# AC-DC_SUPPLY.net
KiCad netlist of a schematic drawn in Altium Designer
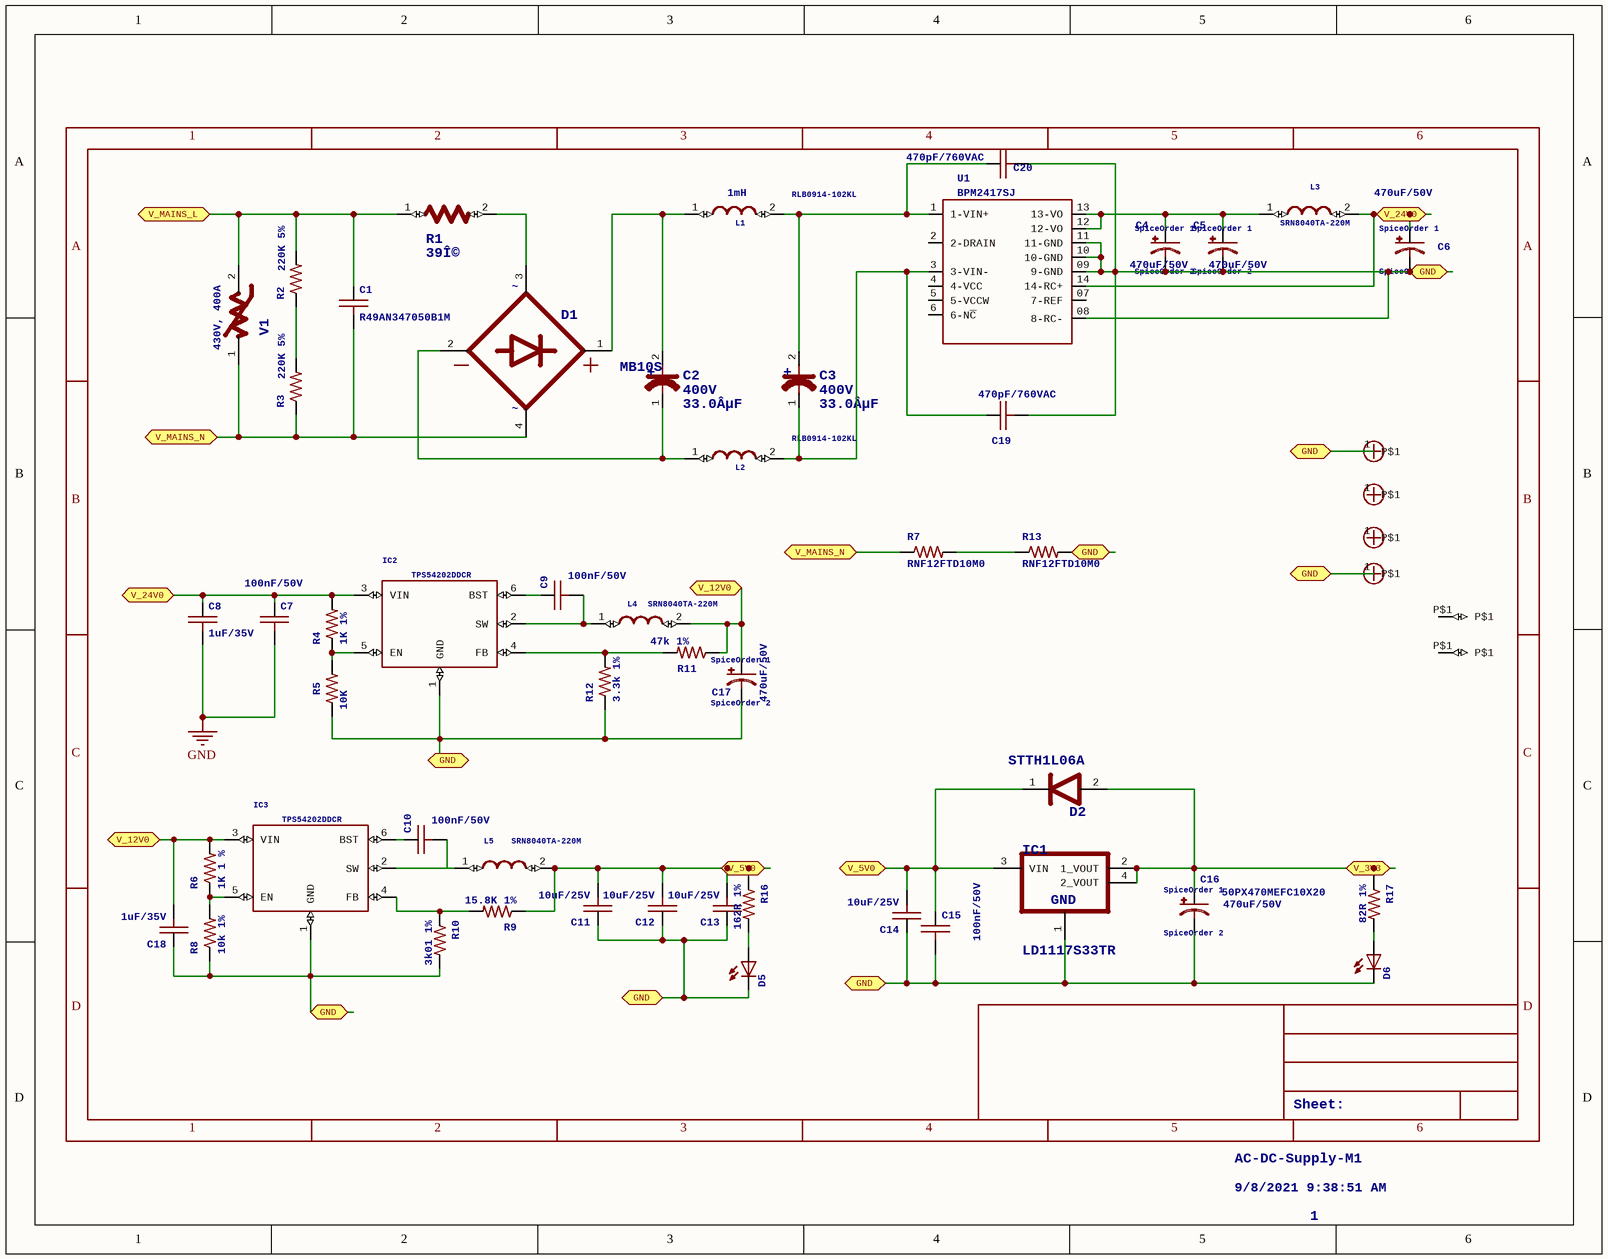
[diagram p0: AC-DC_SUPPLY.SchDoc]

(export (version "E")
  (design (tool "Eeschema 10.0.6"))
  (components
    (comp (ref "C1")
      (value "R49AN347050B1M")
      (footprint "R49AN347050B1M")
      (description "Film,X1,470nF/330Vac,THT")
      (fields (field (name "MFR") "Kemet") (field (name "LIBRARYNAME") "Labops_Lib_AH"))
      (libsource (lib "Labops_Lib_AH") (part "R49AN347050B1M"))
    )
    (comp (ref "C2")
      (value "860011378008")
      (footprint "RADIAL_D13.0P5.0H25.0")
      (description "Electrolytic Cap 33µF 400V 13mm Radial WCAP-ATG8; Lifetime 2000h +85°C")
      (fields
        (field (name "33.0ÂΜF") "33.0碌F")
        (field (name "+") "+")
        (field (name "400V") "400V")
        (field (name "MFR") "Wurth Elektronik")
        (field (name "LIBRARYNAME") "Labops_Lib_AH")
      )
      (libsource (lib "Labops_Lib_AH") (part "860011378008"))
    )
    (comp (ref "C3")
      (value "860011378008")
      (footprint "RADIAL_D13.0P5.0H25.0")
      (description "Electrolytic Cap 33µF 400V 13mm Radial WCAP-ATG8; Lifetime 2000h +85°C")
      (fields
        (field (name "33.0ÂΜF") "33.0碌F")
        (field (name "+") "+")
        (field (name "400V") "400V")
        (field (name "MFR") "Wurth Elektronik")
        (field (name "LIBRARYNAME") "Labops_Lib_AH")
      )
      (libsource (lib "Labops_Lib_AH") (part "860011378008"))
    )
    (comp (ref "C4")
      (value "50PX470MEFC10X20")
      (footprint "CAPACITOR-ELKO-RM5-10X16")
      (description "470uF ±20% 50V 10mm 20mm 5mm 2000Hrs")
      (fields
        (field (name "SPICEORDER1") "SpiceOrder 1")
        (field (name "SPICEORDER2") "SpiceOrder 2")
        (field (name "MFR") "Rubicon")
        (field (name "PART_VALUE") "470uF/50V")
        (field (name "LIBRARYNAME") "Labops_Lib_AH")
      )
      (libsource (lib "Labops_Lib_AH") (part "50PX470MEFC10X20"))
    )
    (comp (ref "C5")
      (value "50PX470MEFC10X20")
      (footprint "CAPACITOR-ELKO-RM5-10X16")
      (description "470uF ±20% 50V 10mm 20mm 5mm 2000Hrs")
      (fields
        (field (name "SPICEORDER1") "SpiceOrder 1")
        (field (name "SPICEORDER2") "SpiceOrder 2")
        (field (name "MFR") "Rubicon")
        (field (name "PART_VALUE") "470uF/50V")
        (field (name "LIBRARYNAME") "Labops_Lib_AH")
      )
      (libsource (lib "Labops_Lib_AH") (part "50PX470MEFC10X20"))
    )
    (comp (ref "C6")
      (value "50PX470MEFC10X20")
      (footprint "CAPACITOR-ELKO-RM5-10X16")
      (description "470uF ±20% 50V 10mm 20mm 5mm 2000Hrs")
      (fields
        (field (name "SPICEORDER1") "SpiceOrder 1")
        (field (name "SPICEORDER2") "SpiceOrder 2")
        (field (name "MFR") "Rubicon")
        (field (name "PART_VALUE") "470uF/50V")
        (field (name "LIBRARYNAME") "Labops_Lib_AH")
      )
      (libsource (lib "Labops_Lib_AH") (part "50PX470MEFC10X20"))
    )
    (comp (ref "C7")
      (value "100nF/50V")
      (footprint "0603")
      (fields (field (name "LIBRARYNAME") "Labops_Lib_AH"))
      (libsource (lib "Labops_Lib_AH") (part "C_0603"))
    )
    (comp (ref "C8")
      (value "1uF/35V")
      (footprint "0603")
      (fields (field (name "LIBRARYNAME") "Labops_Lib_AH"))
      (libsource (lib "Labops_Lib_AH") (part "C_0603"))
    )
    (comp (ref "C9")
      (value "100nF/50V")
      (footprint "0603")
      (fields (field (name "LIBRARYNAME") "Labops_Lib_AH"))
      (libsource (lib "Labops_Lib_AH") (part "C_0603"))
    )
    (comp (ref "C10")
      (value "100nF/50V")
      (footprint "0603")
      (fields (field (name "LIBRARYNAME") "Labops_Lib_AH"))
      (libsource (lib "Labops_Lib_AH") (part "C_0603"))
    )
    (comp (ref "C11")
      (value "10uF/25V")
      (footprint "0603")
      (fields (field (name "LIBRARYNAME") "Labops_Lib_AH"))
      (libsource (lib "Labops_Lib_AH") (part "C_0603"))
    )
    (comp (ref "C12")
      (value "10uF/25V")
      (footprint "0603")
      (fields (field (name "LIBRARYNAME") "Labops_Lib_AH"))
      (libsource (lib "Labops_Lib_AH") (part "C_0603"))
    )
    (comp (ref "C13")
      (value "10uF/25V")
      (footprint "0603")
      (fields (field (name "LIBRARYNAME") "Labops_Lib_AH"))
      (libsource (lib "Labops_Lib_AH") (part "C_0603"))
    )
    (comp (ref "C14")
      (value "10uF/25V")
      (footprint "0603")
      (fields (field (name "LIBRARYNAME") "Labops_Lib_AH"))
      (libsource (lib "Labops_Lib_AH") (part "C_0603"))
    )
    (comp (ref "C15")
      (value "100nF/50V")
      (footprint "0603")
      (fields (field (name "LIBRARYNAME") "Labops_Lib_AH"))
      (libsource (lib "Labops_Lib_AH") (part "C_0603"))
    )
    (comp (ref "C16")
      (value "50PX470MEFC10X20")
      (footprint "CAPACITOR-ELKO-RM5-10X16")
      (description "470uF ±20% 50V 10mm 20mm 5mm 2000Hrs")
      (fields
        (field (name "SPICEORDER1") "SpiceOrder 1")
        (field (name "SPICEORDER2") "SpiceOrder 2")
        (field (name "MFR") "Rubicon")
        (field (name "PART_VALUE") "470uF/50V")
        (field (name "LIBRARYNAME") "Labops_Lib_AH")
      )
      (libsource (lib "Labops_Lib_AH") (part "50PX470MEFC10X20"))
    )
    (comp (ref "C17")
      (value "50PX470MEFC10X20")
      (footprint "CAPACITOR-ELKO-RM5-10X16")
      (description "470uF ±20% 50V 10mm 20mm 5mm 2000Hrs")
      (fields
        (field (name "SPICEORDER1") "SpiceOrder 1")
        (field (name "SPICEORDER2") "SpiceOrder 2")
        (field (name "MFR") "Rubicon")
        (field (name "PART_VALUE") "470uF/50V")
        (field (name "LIBRARYNAME") "Labops_Lib_AH")
      )
      (libsource (lib "Labops_Lib_AH") (part "50PX470MEFC10X20"))
    )
    (comp (ref "C18")
      (value "1uF/35V")
      (footprint "0603")
      (fields (field (name "LIBRARYNAME") "Labops_Lib_AH"))
      (libsource (lib "Labops_Lib_AH") (part "C_0603"))
    )
    (comp (ref "C19")
      (value "ERP610W471MEF0")
      (footprint "CAP-P12.5-H15-W4-D1")
      (description "470 pF ±20% 760VAC Ceramic Capacitor Y5U (E) Radial X1,Y1")
      (fields
        (field (name "MFR") "Kemet")
        (field (name "PART_VALUE") "470pF/760VAC")
        (field (name "LIBRARYNAME") "Labops_Lib_AH")
      )
      (libsource (lib "Labops_Lib_AH") (part "ERP610W471MEF0"))
    )
    (comp (ref "C20")
      (value "ERP610W471MEF0")
      (footprint "CAP-P12.5-H15-W4-D1")
      (description "470 pF ±20% 760VAC Ceramic Capacitor Y5U (E) Radial X1,Y1")
      (fields
        (field (name "MFR") "Kemet")
        (field (name "PART_VALUE") "470pF/760VAC")
        (field (name "LIBRARYNAME") "Labops_Lib_AH")
      )
      (libsource (lib "Labops_Lib_AH") (part "ERP610W471MEF0"))
    )
    (comp (ref "D1")
      (value "MB10S")
      (footprint "SOIC4W")
      (description "0.5 A 1000 V Low Leakage SMT Bridge Rectifier - SOIC-4")
      (fields
        (field (name "MB10S") "MB10S")
        (field (name "MFR") "On Semi, Diodes,MDD")
        (field (name "LIBRARYNAME") "Labops_Lib_AH")
      )
      (libsource (lib "Labops_Lib_AH") (part "MB10S"))
    )
    (comp (ref "D2")
      (value "STTH1L06ASTMICROELECTRONICS_STTH1L06A_0_0")
      (footprint "SMA_STTH1L06A")
      (description "Diode Standard 600V 1A Surface Mount SMA")
      (fields
        (field (name "STTH1L06A") "STTH1L06A")
        (field (name "DIGIKEY_PART_NUMBER") "497-3241-2-ND")
        (field (name "MF") "STMicroelectronics")
        (field (name "LIBRARYNAME") "Labops_Lib_AH")
      )
      (libsource (lib "Labops_Lib_AH") (part "STTH1L06ASTMICROELECTRONICS_STTH1L06A_0_0"))
    )
    (comp (ref "D5")
      (value "26-21/GPC-F3138B/CA")
      (footprint "SMD1206-LED")
      (description "Green SMD LED 1206, 160mcd")
      (fields (field (name "MFR") "Everlight") (field (name "LIBRARYNAME") "Labops_Lib_AH"))
      (libsource (lib "Labops_Lib_AH") (part "26-21/GPC-F3138B/CA"))
    )
    (comp (ref "D6")
      (value "26-21/GPC-F3138B/CA")
      (footprint "SMD1206-LED")
      (description "Green SMD LED 1206, 160mcd")
      (fields (field (name "MFR") "Everlight") (field (name "LIBRARYNAME") "Labops_Lib_AH"))
      (libsource (lib "Labops_Lib_AH") (part "26-21/GPC-F3138B/CA"))
    )
    (comp (ref "FID1")
      (value "FIDUCIAL")
      (footprint "FIDUCIAL")
      (fields (field (name "LIBRARYNAME") "Labops_Lib_AH"))
      (libsource (lib "Labops_Lib_AH") (part "FIDUCIAL"))
    )
    (comp (ref "FID2")
      (value "FIDUCIAL")
      (footprint "FIDUCIAL")
      (fields (field (name "LIBRARYNAME") "Labops_Lib_AH"))
      (libsource (lib "Labops_Lib_AH") (part "FIDUCIAL"))
    )
    (comp (ref "IC1")
      (value "LD1117S33TR")
      (footprint "SOT223_LD1117S33TR")
      (description "LDO,Fixed 15V 3.3V 1.3V")
      (fields
        (field (name "GND") "GND")
        (field (name "LD1117S33TR") "LD1117S33TR")
        (field (name "MFR") "STmicro, Diodes, TI,")
        (field (name "LIBRARYNAME") "Labops_Lib_AH")
      )
      (libsource (lib "Labops_Lib_AH") (part "LD1117S33TR"))
    )
    (comp (ref "IC2")
      (value "TPS54202DDCR")
      (footprint "SOT23-6")
      (description "2A 28V SOT-23-6 Sync Buck")
      (fields (field (name "MFR") "Texas Instruments") (field (name "LIBRARYNAME") "Labops_Lib_AH"))
      (libsource (lib "Labops_Lib_AH") (part "TPS54202DDCR"))
    )
    (comp (ref "IC3")
      (value "TPS54202DDCR")
      (footprint "SOT23-6")
      (description "2A 28V SOT-23-6 Sync Buck")
      (fields (field (name "MFR") "Texas Instruments") (field (name "LIBRARYNAME") "Labops_Lib_AH"))
      (libsource (lib "Labops_Lib_AH") (part "TPS54202DDCR"))
    )
    (comp (ref "L1")
      (value "RLB0914-102KL")
      (footprint "THTINDUCTOR8MM7")
      (description "Inductor Power Wirewound 1mH 10% 252KHz 40Q-Factor Ferrite 300mA 2.1Ohm")
      (fields
        (field (name "MFR") "Bourns")
        (field (name "PART_VALUE") "1mH")
        (field (name "LIBRARYNAME") "Labops_Lib_AH")
      )
      (libsource (lib "Labops_Lib_AH") (part "RLB0914-102KL"))
    )
    (comp (ref "L2")
      (value "RLB0914-102KL")
      (footprint "THTINDUCTOR8MM7")
      (description "Inductor Power Wirewound 1mH 10% 252KHz 40Q-Factor Ferrite 300mA 2.1Ohm")
      (fields (field (name "MFR") "Bourns") (field (name "LIBRARYNAME") "Labops_Lib_AH"))
      (libsource (lib "Labops_Lib_AH") (part "RLB0914-102KL"))
    )
    (comp (ref "L3")
      (value "SRN8040TA-220M")
      (footprint "SRN8040TA-220M")
      (description "FIXED IND 22UH 2.9A SMD, 73m-Ohm, Bourns")
      (fields (field (name "MFR") "Bourns") (field (name "LIBRARYNAME") "Labops_Lib_AH"))
      (libsource (lib "Labops_Lib_AH") (part "SRN8040TA-220M"))
    )
    (comp (ref "L4")
      (value "SRN8040TA-220M")
      (footprint "SRN8040TA-220M")
      (description "FIXED IND 22UH 2.9A SMD, 73m-Ohm, Bourns")
      (fields (field (name "MFR") "Bourns") (field (name "LIBRARYNAME") "Labops_Lib_AH"))
      (libsource (lib "Labops_Lib_AH") (part "SRN8040TA-220M"))
    )
    (comp (ref "L5")
      (value "SRN8040TA-220M")
      (footprint "SRN8040TA-220M")
      (description "FIXED IND 22UH 2.9A SMD, 73m-Ohm, Bourns")
      (fields (field (name "MFR") "Bourns") (field (name "LIBRARYNAME") "Labops_Lib_AH"))
      (libsource (lib "Labops_Lib_AH") (part "SRN8040TA-220M"))
    )
    (comp (ref "M1")
      (value "M_HOLE_3M")
      (footprint "PCB_SCREW_M3_POWER")
      (fields (field (name "LIBRARYNAME") "Labops_Lib_AH"))
      (libsource (lib "Labops_Lib_AH") (part "M_HOLE_3M"))
    )
    (comp (ref "M2")
      (value "M_HOLE_3M")
      (footprint "PCB_SCREW_M3_POWER")
      (fields (field (name "LIBRARYNAME") "Labops_Lib_AH"))
      (libsource (lib "Labops_Lib_AH") (part "M_HOLE_3M"))
    )
    (comp (ref "M3")
      (value "M_HOLE_3M")
      (footprint "PCB_SCREW_M3_POWER")
      (fields (field (name "LIBRARYNAME") "Labops_Lib_AH"))
      (libsource (lib "Labops_Lib_AH") (part "M_HOLE_3M"))
    )
    (comp (ref "M4")
      (value "M_HOLE_3M")
      (footprint "PCB_SCREW_M3_POWER")
      (fields (field (name "LIBRARYNAME") "Labops_Lib_AH"))
      (libsource (lib "Labops_Lib_AH") (part "M_HOLE_3M"))
    )
    (comp (ref "R1")
      (value "ERG-2SJ390V")
      (footprint "ERG-2SJ390V_0")
      (description "RES 39 OHM 2W 5% AXIAL, Metal Oxide, Panasonic")
      (fields (field (name "39惟") "39惟") (field (name "LIBRARYNAME") "Labops_Lib_AH"))
      (libsource (lib "Labops_Lib_AH") (part "ERG-2SJ390V"))
    )
    (comp (ref "R2")
      (value "R_1206")
      (footprint "R1206")
      (fields
        (field (name "MFR") "Vishay")
        (field (name "PART_VALUE") "220K 5%")
        (field (name "LIBRARYNAME") "Labops_Lib_AH")
      )
      (libsource (lib "Labops_Lib_AH") (part "R_1206"))
    )
    (comp (ref "R3")
      (value "R_1206")
      (footprint "R1206")
      (fields
        (field (name "MFR") "Vishay")
        (field (name "PART_VALUE") "220K 5%")
        (field (name "LIBRARYNAME") "Labops_Lib_AH")
      )
      (libsource (lib "Labops_Lib_AH") (part "R_1206"))
    )
    (comp (ref "R4")
      (value "1K 1%")
      (footprint "R0603")
      (fields (field (name "LIBRARYNAME") "Labops_Lib_AH"))
      (libsource (lib "Labops_Lib_AH") (part "R_0603"))
    )
    (comp (ref "R5")
      (value "10K")
      (footprint "R0603")
      (fields (field (name "LIBRARYNAME") "Labops_Lib_AH"))
      (libsource (lib "Labops_Lib_AH") (part "R_0603"))
    )
    (comp (ref "R6")
      (value "1K 1 %")
      (footprint "R0603")
      (fields (field (name "LIBRARYNAME") "Labops_Lib_AH"))
      (libsource (lib "Labops_Lib_AH") (part "R_0603"))
    )
    (comp (ref "R7")
      (value "RNF12FTD10M0")
      (footprint "RES-RM12.5-VR37")
      (description "10 MOhms ±1% 0.5W, 1/2W Through Hole Resistor Axial Flame Retardant Coating, Safety Metal Film")
      (fields (field (name "MFR") "Stackpole Electronics Inc") (field (name "LIBRARYNAME") "Labops_Lib_AH"))
      (libsource (lib "Labops_Lib_AH") (part "RNF12FTD10M0"))
    )
    (comp (ref "R8")
      (value "10k 1%")
      (footprint "R0603")
      (fields (field (name "LIBRARYNAME") "Labops_Lib_AH"))
      (libsource (lib "Labops_Lib_AH") (part "R_0603"))
    )
    (comp (ref "R9")
      (value "15.8K 1%")
      (footprint "R0603")
      (fields (field (name "LIBRARYNAME") "Labops_Lib_AH"))
      (libsource (lib "Labops_Lib_AH") (part "R_0603"))
    )
    (comp (ref "R10")
      (value "3k01 1%")
      (footprint "R0603")
      (fields (field (name "LIBRARYNAME") "Labops_Lib_AH"))
      (libsource (lib "Labops_Lib_AH") (part "R_0603"))
    )
    (comp (ref "R11")
      (value "47k 1%")
      (footprint "R0603")
      (fields (field (name "LIBRARYNAME") "Labops_Lib_AH"))
      (libsource (lib "Labops_Lib_AH") (part "R_0603"))
    )
    (comp (ref "R12")
      (value "3.3k 1%")
      (footprint "R0603")
      (fields (field (name "LIBRARYNAME") "Labops_Lib_AH"))
      (libsource (lib "Labops_Lib_AH") (part "R_0603"))
    )
    (comp (ref "R13")
      (value "RNF12FTD10M0")
      (footprint "RES-RM12.5-VR37")
      (description "10 MOhms ±1% 0.5W, 1/2W Through Hole Resistor Axial Flame Retardant Coating, Safety Metal Film")
      (fields (field (name "MFR") "Stackpole Electronics Inc") (field (name "LIBRARYNAME") "Labops_Lib_AH"))
      (libsource (lib "Labops_Lib_AH") (part "RNF12FTD10M0"))
    )
    (comp (ref "R16")
      (value "162R 1%")
      (footprint "R0603")
      (fields (field (name "LIBRARYNAME") "Labops_Lib_AH"))
      (libsource (lib "Labops_Lib_AH") (part "R_0603"))
    )
    (comp (ref "R17")
      (value "82R 1%")
      (footprint "R0603")
      (fields (field (name "LIBRARYNAME") "Labops_Lib_AH"))
      (libsource (lib "Labops_Lib_AH") (part "R_0603"))
    )
    (comp (ref "U1")
      (value "BPM2417SJ")
      (footprint "BPM2417SJ")
      (description "Ac/Dc Power Supply Module")
      (fields (field (name "MFR") "Tamura") (field (name "LIBRARYNAME") "Labops_Lib_AH"))
      (libsource (lib "Labops_Lib_AH") (part "BPM2417SJ"))
    )
    (comp (ref "V1")
      (value "B72205S0271K101")
      (footprint "EPCOS_B72205S0271K101_0")
      (description "VARISTOR 205V 800A DISC 5MM")
      (fields
        (field (name "MFR") "EPCOS")
        (field (name "PART_VALUE") "430V, 400A")
        (field (name "LIBRARYNAME") "Labops_Lib_AH")
      )
      (libsource (lib "Labops_Lib_AH") (part "B72205S0271K101"))
    )
  )
  (nets
    (net (code "1") (name "/V_3V3") (class "Default")
      (node (ref "C16") (pin "1") (pinfunction "+_1") (pintype "passive"))
      (node (ref "D2") (pin "2") (pinfunction "ANODE_2") (pintype "passive"))
      (node (ref "IC1") (pin "2") (pinfunction "1_VOUT_2") (pintype "power_in"))
      (node (ref "IC1") (pin "4") (pinfunction "2_VOUT_4") (pintype "power_in"))
      (node (ref "R17") (pin "1") (pinfunction "1_1") (pintype "passive"))
    )
    (net (code "2") (name "/V_5V0") (class "Default")
      (node (ref "C11") (pin "2") (pinfunction "2_2") (pintype "passive"))
      (node (ref "C12") (pin "2") (pinfunction "2_2") (pintype "passive"))
      (node (ref "C13") (pin "2") (pinfunction "2_2") (pintype "passive"))
      (node (ref "C14") (pin "2") (pinfunction "2_2") (pintype "passive"))
      (node (ref "C15") (pin "1") (pinfunction "1_1") (pintype "passive"))
      (node (ref "D2") (pin "1") (pinfunction "CATHODE_1") (pintype "passive"))
      (node (ref "IC1") (pin "3") (pinfunction "VIN_3") (pintype "power_in"))
      (node (ref "L5") (pin "2") (pinfunction "P$2_2") (pintype "bidirectional"))
      (node (ref "R16") (pin "1") (pinfunction "1_1") (pintype "passive"))
      (node (ref "R9") (pin "1") (pinfunction "1_1") (pintype "passive"))
    )
    (net (code "3") (name "/V_12V0") (class "Default")
      (node (ref "C17") (pin "1") (pinfunction "+_1") (pintype "passive"))
      (node (ref "C18") (pin "2") (pinfunction "2_2") (pintype "passive"))
      (node (ref "IC3") (pin "3") (pinfunction "VIN_3") (pintype "bidirectional"))
      (node (ref "L4") (pin "2") (pinfunction "P$2_2") (pintype "bidirectional"))
      (node (ref "R11") (pin "1") (pinfunction "1_1") (pintype "passive"))
      (node (ref "R6") (pin "2") (pinfunction "2_2") (pintype "passive"))
    )
    (net (code "4") (name "/V_24V0") (class "Default")
      (node (ref "C6") (pin "1") (pinfunction "+_1") (pintype "passive"))
      (node (ref "C7") (pin "1") (pinfunction "1_1") (pintype "passive"))
      (node (ref "C8") (pin "1") (pinfunction "1_1") (pintype "passive"))
      (node (ref "IC2") (pin "3") (pinfunction "VIN_3") (pintype "bidirectional"))
      (node (ref "L3") (pin "2") (pinfunction "P$2_2") (pintype "bidirectional"))
      (node (ref "R4") (pin "2") (pinfunction "2_2") (pintype "passive"))
      (node (ref "U1") (pin "14") (pinfunction "14-RC+_14") (pintype "bidirectional"))
    )
    (net (code "5") (name "/V_MAINS_L") (class "Default")
      (node (ref "C1") (pin "1") (pinfunction "1_1") (pintype "passive"))
      (node (ref "R1") (pin "1") (pinfunction "1_1") (pintype "bidirectional"))
      (node (ref "R2") (pin "2") (pinfunction "2_2") (pintype "passive"))
      (node (ref "V1") (pin "2") (pinfunction "2_2") (pintype "passive"))
    )
    (net (code "6") (name "/V_MAINS_N") (class "Default")
      (node (ref "C1") (pin "2") (pinfunction "2_2") (pintype "passive"))
      (node (ref "D1") (pin "4") (pinfunction "2_~_4") (pintype "passive"))
      (node (ref "R3") (pin "1") (pinfunction "1_1") (pintype "passive"))
      (node (ref "R7") (pin "1") (pinfunction "1_1") (pintype "passive"))
      (node (ref "V1") (pin "1") (pinfunction "1_1") (pintype "passive"))
    )
    (net (code "7") (name "GND") (class "Default")
      (node (ref "C11") (pin "1") (pinfunction "1_1") (pintype "passive"))
      (node (ref "C12") (pin "1") (pinfunction "1_1") (pintype "passive"))
      (node (ref "C13") (pin "1") (pinfunction "1_1") (pintype "passive"))
      (node (ref "C14") (pin "1") (pinfunction "1_1") (pintype "passive"))
      (node (ref "C15") (pin "2") (pinfunction "2_2") (pintype "passive"))
      (node (ref "C16") (pin "2") (pinfunction "-_2") (pintype "passive"))
      (node (ref "C17") (pin "2") (pinfunction "-_2") (pintype "passive"))
      (node (ref "C18") (pin "1") (pinfunction "1_1") (pintype "passive"))
      (node (ref "C19") (pin "P$2") (pinfunction "2_P$2") (pintype "passive"))
      (node (ref "C20") (pin "P$2") (pinfunction "2_P$2") (pintype "passive"))
      (node (ref "C4") (pin "2") (pinfunction "-_2") (pintype "passive"))
      (node (ref "C5") (pin "2") (pinfunction "-_2") (pintype "passive"))
      (node (ref "C6") (pin "2") (pinfunction "-_2") (pintype "passive"))
      (node (ref "C7") (pin "2") (pinfunction "2_2") (pintype "passive"))
      (node (ref "C8") (pin "2") (pinfunction "2_2") (pintype "passive"))
      (node (ref "D5") (pin "2") (pinfunction "C_2") (pintype "passive"))
      (node (ref "D6") (pin "2") (pinfunction "C_2") (pintype "passive"))
      (node (ref "IC1") (pin "1") (pinfunction "GND_1") (pintype "power_in"))
      (node (ref "IC2") (pin "1") (pinfunction "GND_1") (pintype "bidirectional"))
      (node (ref "IC3") (pin "1") (pinfunction "GND_1") (pintype "bidirectional"))
      (node (ref "M1") (pin "1") (pinfunction "P$1_1") (pintype "bidirectional"))
      (node (ref "M4") (pin "1") (pinfunction "P$1_1") (pintype "bidirectional"))
      (node (ref "R10") (pin "2") (pinfunction "2_2") (pintype "passive"))
      (node (ref "R12") (pin "1") (pinfunction "1_1") (pintype "passive"))
      (node (ref "R13") (pin "2") (pinfunction "2_2") (pintype "passive"))
      (node (ref "R5") (pin "1") (pinfunction "1_1") (pintype "passive"))
      (node (ref "R8") (pin "1") (pinfunction "1_1") (pintype "passive"))
      (node (ref "U1") (pin "08") (pinfunction "8-RC-_08") (pintype "bidirectional"))
      (node (ref "U1") (pin "09") (pinfunction "9-GND_09") (pintype "bidirectional"))
      (node (ref "U1") (pin "10") (pinfunction "10-GND_10") (pintype "bidirectional"))
      (node (ref "U1") (pin "11") (pinfunction "11-GND_11") (pintype "bidirectional"))
    )
    (net (code "8") (name "Net-(C2-ANODE)") (class "Default")
      (node (ref "C2") (pin "2") (pinfunction "ANODE_2") (pintype "passive"))
      (node (ref "D1") (pin "1") (pinfunction "+_1") (pintype "passive"))
      (node (ref "L1") (pin "1") (pinfunction "P$1_1") (pintype "bidirectional"))
    )
    (net (code "9") (name "Net-(C2-CATHODE)") (class "Default")
      (node (ref "C2") (pin "1") (pinfunction "CATHODE_1") (pintype "passive"))
      (node (ref "D1") (pin "2") (pinfunction "-_2") (pintype "passive"))
      (node (ref "L2") (pin "1") (pinfunction "P$1_1") (pintype "bidirectional"))
    )
    (net (code "10") (name "Net-(C4-+)") (class "Default")
      (node (ref "C4") (pin "1") (pinfunction "+_1") (pintype "passive"))
      (node (ref "C5") (pin "1") (pinfunction "+_1") (pintype "passive"))
      (node (ref "L3") (pin "1") (pinfunction "P$1_1") (pintype "bidirectional"))
      (node (ref "U1") (pin "12") (pinfunction "12-VO_12") (pintype "bidirectional"))
      (node (ref "U1") (pin "13") (pinfunction "13-VO_13") (pintype "bidirectional"))
    )
    (net (code "11") (name "Net-(C19-1)") (class "Default")
      (node (ref "C19") (pin "P$1") (pinfunction "1_P$1") (pintype "passive"))
      (node (ref "C3") (pin "1") (pinfunction "CATHODE_1") (pintype "passive"))
      (node (ref "L2") (pin "2") (pinfunction "P$2_2") (pintype "bidirectional"))
      (node (ref "U1") (pin "3") (pinfunction "3-VIN-_3") (pintype "bidirectional"))
    )
    (net (code "12") (name "Net-(C20-1)") (class "Default")
      (node (ref "C20") (pin "P$1") (pinfunction "1_P$1") (pintype "passive"))
      (node (ref "C3") (pin "2") (pinfunction "ANODE_2") (pintype "passive"))
      (node (ref "L1") (pin "2") (pinfunction "P$2_2") (pintype "bidirectional"))
      (node (ref "U1") (pin "1") (pinfunction "1-VIN+_1") (pintype "bidirectional"))
    )
    (net (code "13") (name "Net-(D1-1_~)") (class "Default")
      (node (ref "D1") (pin "3") (pinfunction "1_~_3") (pintype "passive"))
      (node (ref "R1") (pin "2") (pinfunction "2_2") (pintype "bidirectional"))
    )
    (net (code "14") (name "Net-(D5-A)") (class "Default")
      (node (ref "D5") (pin "1") (pinfunction "A_1") (pintype "passive"))
      (node (ref "R16") (pin "2") (pinfunction "2_2") (pintype "passive"))
    )
    (net (code "15") (name "Net-(D6-A)") (class "Default")
      (node (ref "D6") (pin "1") (pinfunction "A_1") (pintype "passive"))
      (node (ref "R17") (pin "2") (pinfunction "2_2") (pintype "passive"))
    )
    (net (code "16") (name "Net-(IC2-BST)") (class "Default")
      (node (ref "C9") (pin "1") (pinfunction "1_1") (pintype "passive"))
      (node (ref "IC2") (pin "6") (pinfunction "BST_6") (pintype "bidirectional"))
    )
    (net (code "17") (name "Net-(IC2-EN)") (class "Default")
      (node (ref "IC2") (pin "5") (pinfunction "EN_5") (pintype "bidirectional"))
      (node (ref "R4") (pin "1") (pinfunction "1_1") (pintype "passive"))
      (node (ref "R5") (pin "2") (pinfunction "2_2") (pintype "passive"))
    )
    (net (code "18") (name "Net-(IC2-FB)") (class "Default")
      (node (ref "IC2") (pin "4") (pinfunction "FB_4") (pintype "bidirectional"))
      (node (ref "R11") (pin "2") (pinfunction "2_2") (pintype "passive"))
      (node (ref "R12") (pin "2") (pinfunction "2_2") (pintype "passive"))
    )
    (net (code "19") (name "Net-(IC2-SW)") (class "Default")
      (node (ref "C9") (pin "2") (pinfunction "2_2") (pintype "passive"))
      (node (ref "IC2") (pin "2") (pinfunction "SW_2") (pintype "bidirectional"))
      (node (ref "L4") (pin "1") (pinfunction "P$1_1") (pintype "bidirectional"))
    )
    (net (code "20") (name "Net-(IC3-BST)") (class "Default")
      (node (ref "C10") (pin "1") (pinfunction "1_1") (pintype "passive"))
      (node (ref "IC3") (pin "6") (pinfunction "BST_6") (pintype "bidirectional"))
    )
    (net (code "21") (name "Net-(IC3-EN)") (class "Default")
      (node (ref "IC3") (pin "5") (pinfunction "EN_5") (pintype "bidirectional"))
      (node (ref "R6") (pin "1") (pinfunction "1_1") (pintype "passive"))
      (node (ref "R8") (pin "2") (pinfunction "2_2") (pintype "passive"))
    )
    (net (code "22") (name "Net-(IC3-FB)") (class "Default")
      (node (ref "IC3") (pin "4") (pinfunction "FB_4") (pintype "bidirectional"))
      (node (ref "R10") (pin "1") (pinfunction "1_1") (pintype "passive"))
      (node (ref "R9") (pin "2") (pinfunction "2_2") (pintype "passive"))
    )
    (net (code "23") (name "Net-(IC3-SW)") (class "Default")
      (node (ref "C10") (pin "2") (pinfunction "2_2") (pintype "passive"))
      (node (ref "IC3") (pin "2") (pinfunction "SW_2") (pintype "bidirectional"))
      (node (ref "L5") (pin "1") (pinfunction "P$1_1") (pintype "bidirectional"))
    )
    (net (code "24") (name "Net-(R2-Pad1)") (class "Default")
      (node (ref "R2") (pin "1") (pinfunction "1_1") (pintype "passive"))
      (node (ref "R3") (pin "2") (pinfunction "2_2") (pintype "passive"))
    )
    (net (code "25") (name "Net-(R13-Pad1)") (class "Default")
      (node (ref "R13") (pin "1") (pinfunction "1_1") (pintype "passive"))
      (node (ref "R7") (pin "2") (pinfunction "2_2") (pintype "passive"))
    )
    (net (code "26") (name "unconnected-(FID1-PadP$1)") (class "Default")
      (node (ref "FID1") (pin "P$1") (pinfunction "P$1_P$1") (pintype "bidirectional"))
    )
    (net (code "27") (name "unconnected-(FID2-PadP$1)") (class "Default")
      (node (ref "FID2") (pin "P$1") (pinfunction "P$1_P$1") (pintype "bidirectional"))
    )
    (net (code "28") (name "unconnected-(M2-P$1-Pad1)") (class "Default")
      (node (ref "M2") (pin "1") (pinfunction "P$1_1") (pintype "bidirectional"))
    )
    (net (code "29") (name "unconnected-(M3-P$1-Pad1)") (class "Default")
      (node (ref "M3") (pin "1") (pinfunction "P$1_1") (pintype "bidirectional"))
    )
    (net (code "30") (name "unconnected-(U1-2-DRAIN-Pad2)") (class "Default")
      (node (ref "U1") (pin "2") (pinfunction "2-DRAIN_2") (pintype "bidirectional"))
    )
    (net (code "31") (name "unconnected-(U1-4-VCC-Pad4)") (class "Default")
      (node (ref "U1") (pin "4") (pinfunction "4-VCC_4") (pintype "bidirectional"))
    )
    (net (code "32") (name "unconnected-(U1-5-VCCW-Pad5)") (class "Default")
      (node (ref "U1") (pin "5") (pinfunction "5-VCCW_5") (pintype "bidirectional"))
    )
    (net (code "33") (name "unconnected-(U1-6-N~{C}-Pad6)") (class "Default")
      (node (ref "U1") (pin "6") (pinfunction "6-N~{C}_6") (pintype "bidirectional"))
    )
    (net (code "34") (name "unconnected-(U1-7-REF-Pad07)") (class "Default")
      (node (ref "U1") (pin "07") (pinfunction "7-REF_07") (pintype "bidirectional"))
    )
  )
)
